# Sheet_Top_Front.net
KiCad netlist of a schematic drawn in Altium Designer
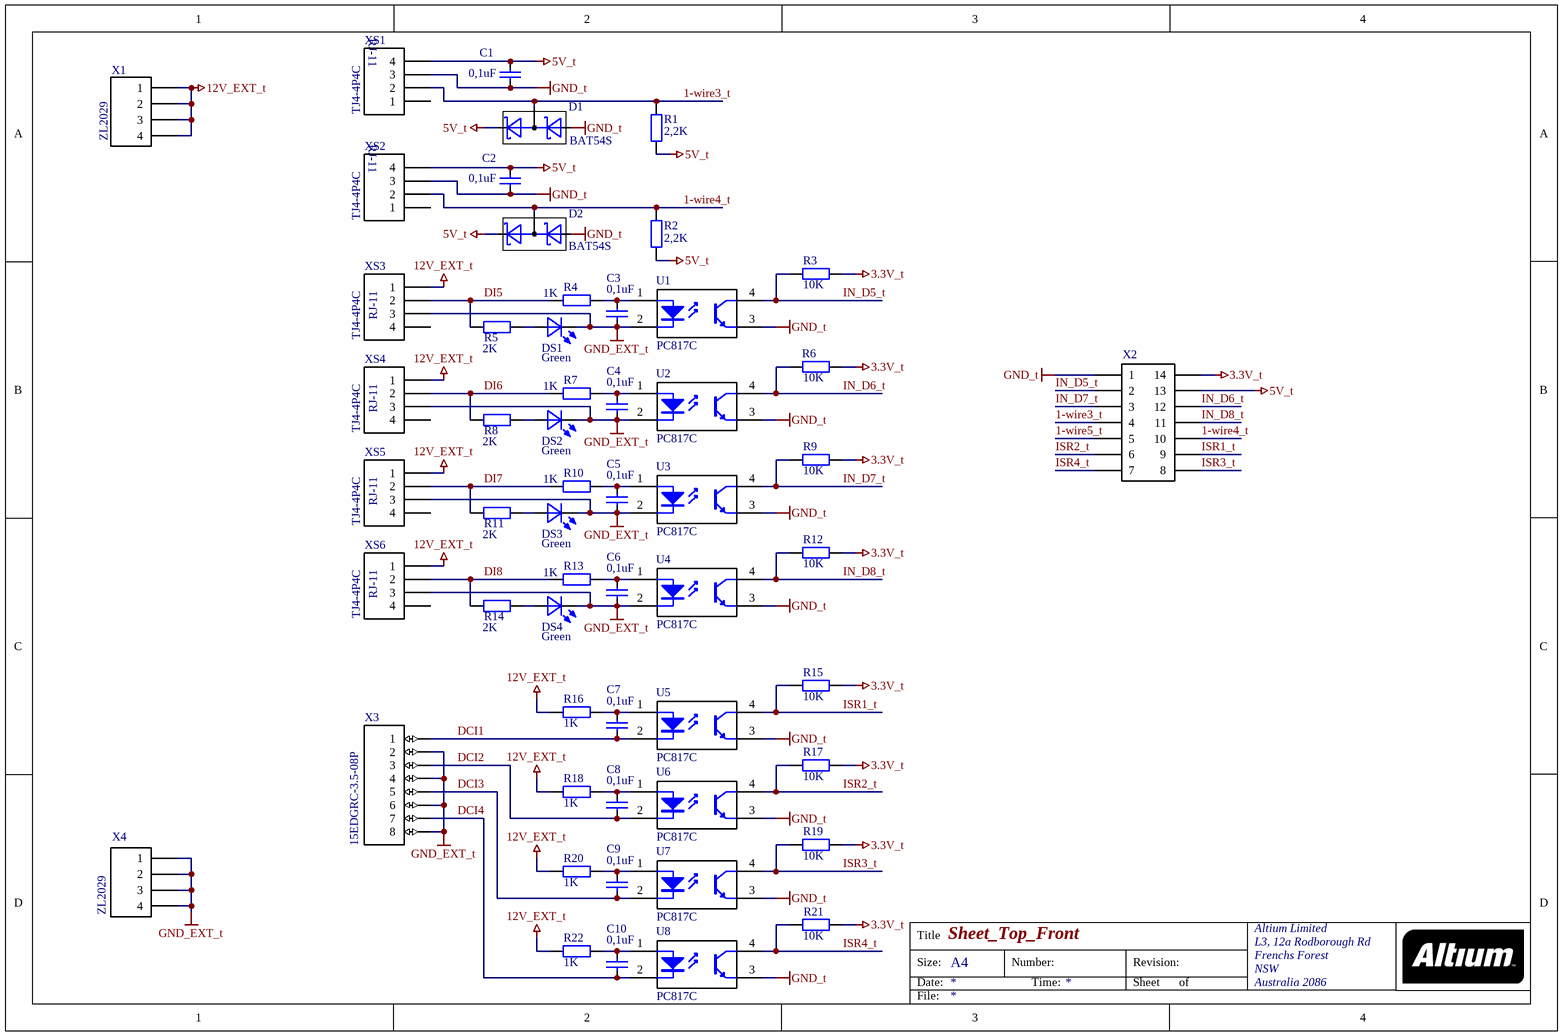
[diagram p0: Sheet_Top_Front.SchDoc]

(export (version "E")
  (design (tool "Eeschema 10.0.6"))
  (components
    (comp (ref "C1")
      (value "0,1uF")
      (footprint "C_0805")
      (description "Capacitor semi")
      (fields (field (name "Comment") "Cap_Semi"))
      (libsource (lib "Capacitor") (part "Cap_Semi"))
    )
    (comp (ref "C2")
      (value "0,1uF")
      (footprint "C_0805")
      (description "Capacitor semi")
      (fields (field (name "Comment") "Cap_Semi"))
      (libsource (lib "Capacitor") (part "Cap_Semi"))
    )
    (comp (ref "C3")
      (value "0,1uF")
      (footprint "C_0805")
      (description "Capacitor semi")
      (fields (field (name "Comment") "Cap_Semi"))
      (libsource (lib "Capacitor") (part "Cap_Semi"))
    )
    (comp (ref "C4")
      (value "0,1uF")
      (footprint "C_0805")
      (description "Capacitor semi")
      (fields (field (name "Comment") "Cap_Semi"))
      (libsource (lib "Capacitor") (part "Cap_Semi"))
    )
    (comp (ref "C5")
      (value "0,1uF")
      (footprint "C_0805")
      (description "Capacitor semi")
      (fields (field (name "Comment") "Cap_Semi"))
      (libsource (lib "Capacitor") (part "Cap_Semi"))
    )
    (comp (ref "C6")
      (value "0,1uF")
      (footprint "C_0805")
      (description "Capacitor semi")
      (fields (field (name "Comment") "Cap_Semi"))
      (libsource (lib "Capacitor") (part "Cap_Semi"))
    )
    (comp (ref "C7")
      (value "0,1uF")
      (footprint "C_0805")
      (description "Capacitor semi")
      (fields (field (name "Comment") "Cap_Semi"))
      (libsource (lib "Capacitor") (part "Cap_Semi"))
    )
    (comp (ref "C8")
      (value "0,1uF")
      (footprint "C_0805")
      (description "Capacitor semi")
      (fields (field (name "Comment") "Cap_Semi"))
      (libsource (lib "Capacitor") (part "Cap_Semi"))
    )
    (comp (ref "C9")
      (value "0,1uF")
      (footprint "C_0805")
      (description "Capacitor semi")
      (fields (field (name "Comment") "Cap_Semi"))
      (libsource (lib "Capacitor") (part "Cap_Semi"))
    )
    (comp (ref "C10")
      (value "0,1uF")
      (footprint "C_0805")
      (description "Capacitor semi")
      (fields (field (name "Comment") "Cap_Semi"))
      (libsource (lib "Capacitor") (part "Cap_Semi"))
    )
    (comp (ref "D1")
      (value "BAT54S")
      (footprint "SOT-23_d")
      (description "Diode Schottky")
      (libsource (lib "Diode") (part "BAT54S"))
    )
    (comp (ref "D2")
      (value "BAT54S")
      (footprint "SOT-23_d")
      (description "Diode Schottky")
      (libsource (lib "Diode") (part "BAT54S"))
    )
    (comp (ref "DS1")
      (value "Green")
      (footprint "LED_SMD_0805")
      (description "LED_SMD")
      (libsource (lib "LEDs") (part "LED"))
    )
    (comp (ref "DS2")
      (value "Green")
      (footprint "LED_SMD_0805")
      (description "LED_SMD")
      (libsource (lib "LEDs") (part "LED"))
    )
    (comp (ref "DS3")
      (value "Green")
      (footprint "LED_SMD_0805")
      (description "LED_SMD")
      (libsource (lib "LEDs") (part "LED"))
    )
    (comp (ref "DS4")
      (value "Green")
      (footprint "LED_SMD_0805")
      (description "LED_SMD")
      (libsource (lib "LEDs") (part "LED"))
    )
    (comp (ref "R1")
      (value "2,2K")
      (footprint "R_0805")
      (description "Resistor")
      (libsource (lib "Resistors") (part "Resistor"))
    )
    (comp (ref "R2")
      (value "2,2K")
      (footprint "R_0805")
      (description "Resistor")
      (libsource (lib "Resistors") (part "Resistor"))
    )
    (comp (ref "R3")
      (value "10K")
      (footprint "R_0805")
      (description "Resistor")
      (libsource (lib "Resistors") (part "Resistor"))
    )
    (comp (ref "R4")
      (value "1K")
      (footprint "R_0805")
      (description "Resistor")
      (libsource (lib "Resistors") (part "Resistor"))
    )
    (comp (ref "R5")
      (value "2K")
      (footprint "R_0805")
      (description "Resistor")
      (libsource (lib "Resistors") (part "Resistor"))
    )
    (comp (ref "R6")
      (value "10K")
      (footprint "R_0805")
      (description "Resistor")
      (libsource (lib "Resistors") (part "Resistor"))
    )
    (comp (ref "R7")
      (value "1K")
      (footprint "R_0805")
      (description "Resistor")
      (libsource (lib "Resistors") (part "Resistor"))
    )
    (comp (ref "R8")
      (value "2K")
      (footprint "R_0805")
      (description "Resistor")
      (libsource (lib "Resistors") (part "Resistor"))
    )
    (comp (ref "R9")
      (value "10K")
      (footprint "R_0805")
      (description "Resistor")
      (libsource (lib "Resistors") (part "Resistor"))
    )
    (comp (ref "R10")
      (value "1K")
      (footprint "R_0805")
      (description "Resistor")
      (libsource (lib "Resistors") (part "Resistor"))
    )
    (comp (ref "R11")
      (value "2K")
      (footprint "R_0805")
      (description "Resistor")
      (libsource (lib "Resistors") (part "Resistor"))
    )
    (comp (ref "R12")
      (value "10K")
      (footprint "R_0805")
      (description "Resistor")
      (libsource (lib "Resistors") (part "Resistor"))
    )
    (comp (ref "R13")
      (value "1K")
      (footprint "R_0805")
      (description "Resistor")
      (libsource (lib "Resistors") (part "Resistor"))
    )
    (comp (ref "R14")
      (value "2K")
      (footprint "R_0805")
      (description "Resistor")
      (libsource (lib "Resistors") (part "Resistor"))
    )
    (comp (ref "R15")
      (value "10K")
      (footprint "R_0805")
      (description "Resistor")
      (libsource (lib "Resistors") (part "Resistor"))
    )
    (comp (ref "R16")
      (value "1K")
      (footprint "R_0805")
      (description "Resistor")
      (libsource (lib "Resistors") (part "Resistor"))
    )
    (comp (ref "R17")
      (value "10K")
      (footprint "R_0805")
      (description "Resistor")
      (libsource (lib "Resistors") (part "Resistor"))
    )
    (comp (ref "R18")
      (value "1K")
      (footprint "R_0805")
      (description "Resistor")
      (libsource (lib "Resistors") (part "Resistor"))
    )
    (comp (ref "R19")
      (value "10K")
      (footprint "R_0805")
      (description "Resistor")
      (libsource (lib "Resistors") (part "Resistor"))
    )
    (comp (ref "R20")
      (value "1K")
      (footprint "R_0805")
      (description "Resistor")
      (libsource (lib "Resistors") (part "Resistor"))
    )
    (comp (ref "R21")
      (value "10K")
      (footprint "R_0805")
      (description "Resistor")
      (libsource (lib "Resistors") (part "Resistor"))
    )
    (comp (ref "R22")
      (value "1K")
      (footprint "R_0805")
      (description "Resistor")
      (libsource (lib "Resistors") (part "Resistor"))
    )
    (comp (ref "U1")
      (value "PC817C")
      (footprint "DIP-4")
      (description "Optocoupler")
      (libsource (lib "Chip_Packaging") (part "PC817"))
    )
    (comp (ref "U2")
      (value "PC817C")
      (footprint "DIP-4")
      (description "Optocoupler")
      (libsource (lib "Chip_Packaging") (part "PC817"))
    )
    (comp (ref "U3")
      (value "PC817C")
      (footprint "DIP-4")
      (description "Optocoupler")
      (libsource (lib "Chip_Packaging") (part "PC817"))
    )
    (comp (ref "U4")
      (value "PC817C")
      (footprint "DIP-4")
      (description "Optocoupler")
      (libsource (lib "Chip_Packaging") (part "PC817"))
    )
    (comp (ref "U5")
      (value "PC817C")
      (footprint "DIP-4")
      (description "Optocoupler")
      (libsource (lib "Chip_Packaging") (part "PC817"))
    )
    (comp (ref "U6")
      (value "PC817C")
      (footprint "DIP-4")
      (description "Optocoupler")
      (libsource (lib "Chip_Packaging") (part "PC817"))
    )
    (comp (ref "U7")
      (value "PC817C")
      (footprint "DIP-4")
      (description "Optocoupler")
      (libsource (lib "Chip_Packaging") (part "PC817"))
    )
    (comp (ref "U8")
      (value "PC817C")
      (footprint "DIP-4")
      (description "Optocoupler")
      (libsource (lib "Chip_Packaging") (part "PC817"))
    )
    (comp (ref "X1")
      (value "ZL2029")
      (footprint "PLS-4-3D")
      (description "Header, 4-Pin")
      (fields (field (name "ALTIUM_UNNAMED_1") "ZL2029") (field (name "PUBLISHER") "Altium Limited"))
      (libsource (lib "Connect") (part "PLS-4"))
    )
    (comp (ref "X2")
      (value "PLS2-14")
      (footprint "PLS2-14")
      (description "Header, 14-Pin")
      (libsource (lib "Connect") (part "PLS2-14"))
    )
    (comp (ref "X3")
      (value "15EDGRC-3.5-08P")
      (footprint "MC_3.5_8")
      (description "Connector 3.5mm")
      (libsource (lib "Connect") (part "MC_3.5_8"))
    )
    (comp (ref "X4")
      (value "PLS-4")
      (footprint "PLS-4-3D")
      (description "ZL2029")
      (fields (field (name "ALTIUM_UNNAMED_1") "ZL2029") (field (name "PUBLISHER") "Altium Limited"))
      (libsource (lib "Connect") (part "PLS-4"))
    )
    (comp (ref "XS1")
      (value "RJ-11")
      (footprint "RJ-11 - TJ4-4P4C")
      (description "TJ4-4P4C")
      (fields (field (name "ALTIUM_UNNAMED_1") "TJ4-4P4C"))
      (libsource (lib "") (part "RJ-11_1"))
    )
    (comp (ref "XS2")
      (value "RJ-11")
      (footprint "RJ-11 - TJ4-4P4C")
      (description "TJ4-4P4C")
      (fields (field (name "ALTIUM_UNNAMED_1") "TJ4-4P4C"))
      (libsource (lib "") (part "RJ-11_1"))
    )
    (comp (ref "XS3")
      (value "RJ-11")
      (footprint "RJ-11 - TJ4-4P4C")
      (description "TJ4-4P4C")
      (fields (field (name "ALTIUM_UNNAMED_1") "TJ4-4P4C"))
      (libsource (lib "Connect") (part "RJ-11"))
    )
    (comp (ref "XS4")
      (value "RJ-11")
      (footprint "RJ-11 - TJ4-4P4C")
      (description "TJ4-4P4C")
      (fields (field (name "ALTIUM_UNNAMED_1") "TJ4-4P4C"))
      (libsource (lib "Connect") (part "RJ-11"))
    )
    (comp (ref "XS5")
      (value "RJ-11")
      (footprint "RJ-11 - TJ4-4P4C")
      (description "TJ4-4P4C")
      (fields (field (name "ALTIUM_UNNAMED_1") "TJ4-4P4C"))
      (libsource (lib "Connect") (part "RJ-11"))
    )
    (comp (ref "XS6")
      (value "RJ-11")
      (footprint "RJ-11 - TJ4-4P4C")
      (description "TJ4-4P4C")
      (fields (field (name "ALTIUM_UNNAMED_1") "TJ4-4P4C"))
      (libsource (lib "Connect") (part "RJ-11"))
    )
  )
  (nets
    (net (code "1") (name "/1-wire3_t") (class "Default")
      (node (ref "D1") (pin "3") (pinfunction "CA_3") (pintype "passive"))
      (node (ref "R1") (pin "1") (pinfunction "1_1") (pintype "passive"))
      (node (ref "X2") (pin "4") (pinfunction "4_4") (pintype "passive"))
      (node (ref "XS1") (pin "2") (pinfunction "2_2") (pintype "passive"))
    )
    (net (code "2") (name "/1-wire4_t") (class "Default")
      (node (ref "D2") (pin "3") (pinfunction "CA_3") (pintype "passive"))
      (node (ref "R2") (pin "1") (pinfunction "1_1") (pintype "passive"))
      (node (ref "X2") (pin "10") (pinfunction "10_10") (pintype "passive"))
      (node (ref "XS2") (pin "2") (pinfunction "2_2") (pintype "passive"))
    )
    (net (code "3") (name "/1-wire5_t") (class "Default")
      (node (ref "X2") (pin "5") (pinfunction "5_5") (pintype "passive"))
    )
    (net (code "4") (name "/DCI1") (class "Default")
      (node (ref "C7") (pin "2") (pinfunction "2_2") (pintype "passive"))
      (node (ref "U5") (pin "2") (pinfunction "K_2") (pintype "passive"))
      (node (ref "X3") (pin "1") (pinfunction "1_1") (pintype "bidirectional"))
    )
    (net (code "5") (name "/DCI2") (class "Default")
      (node (ref "C8") (pin "2") (pinfunction "2_2") (pintype "passive"))
      (node (ref "U6") (pin "2") (pinfunction "K_2") (pintype "passive"))
      (node (ref "X3") (pin "3") (pinfunction "3_3") (pintype "bidirectional"))
    )
    (net (code "6") (name "/DCI3") (class "Default")
      (node (ref "C9") (pin "2") (pinfunction "2_2") (pintype "passive"))
      (node (ref "U7") (pin "2") (pinfunction "K_2") (pintype "passive"))
      (node (ref "X3") (pin "5") (pinfunction "5_5") (pintype "bidirectional"))
    )
    (net (code "7") (name "/DCI4") (class "Default")
      (node (ref "C10") (pin "2") (pinfunction "2_2") (pintype "passive"))
      (node (ref "U8") (pin "2") (pinfunction "K_2") (pintype "passive"))
      (node (ref "X3") (pin "7") (pinfunction "7_7") (pintype "bidirectional"))
    )
    (net (code "8") (name "/DI5") (class "Default")
      (node (ref "R4") (pin "2") (pinfunction "2_2") (pintype "passive"))
      (node (ref "R5") (pin "2") (pinfunction "2_2") (pintype "passive"))
      (node (ref "XS3") (pin "2") (pinfunction "2_2") (pintype "passive"))
    )
    (net (code "9") (name "/DI6") (class "Default")
      (node (ref "R7") (pin "2") (pinfunction "2_2") (pintype "passive"))
      (node (ref "R8") (pin "2") (pinfunction "2_2") (pintype "passive"))
      (node (ref "XS4") (pin "2") (pinfunction "2_2") (pintype "passive"))
    )
    (net (code "10") (name "/DI7") (class "Default")
      (node (ref "R10") (pin "2") (pinfunction "2_2") (pintype "passive"))
      (node (ref "R11") (pin "2") (pinfunction "2_2") (pintype "passive"))
      (node (ref "XS5") (pin "2") (pinfunction "2_2") (pintype "passive"))
    )
    (net (code "11") (name "/DI8") (class "Default")
      (node (ref "R13") (pin "2") (pinfunction "2_2") (pintype "passive"))
      (node (ref "R14") (pin "2") (pinfunction "2_2") (pintype "passive"))
      (node (ref "XS6") (pin "2") (pinfunction "2_2") (pintype "passive"))
    )
    (net (code "12") (name "/IN_D5_t") (class "Default")
      (node (ref "R3") (pin "2") (pinfunction "2_2") (pintype "passive"))
      (node (ref "U1") (pin "4") (pinfunction "C_4") (pintype "passive"))
      (node (ref "X2") (pin "2") (pinfunction "2_2") (pintype "passive"))
    )
    (net (code "13") (name "/IN_D6_t") (class "Default")
      (node (ref "R6") (pin "2") (pinfunction "2_2") (pintype "passive"))
      (node (ref "U2") (pin "4") (pinfunction "C_4") (pintype "passive"))
      (node (ref "X2") (pin "12") (pinfunction "12_12") (pintype "passive"))
    )
    (net (code "14") (name "/IN_D7_t") (class "Default")
      (node (ref "R9") (pin "2") (pinfunction "2_2") (pintype "passive"))
      (node (ref "U3") (pin "4") (pinfunction "C_4") (pintype "passive"))
      (node (ref "X2") (pin "3") (pinfunction "3_3") (pintype "passive"))
    )
    (net (code "15") (name "/IN_D8_t") (class "Default")
      (node (ref "R12") (pin "2") (pinfunction "2_2") (pintype "passive"))
      (node (ref "U4") (pin "4") (pinfunction "C_4") (pintype "passive"))
      (node (ref "X2") (pin "11") (pinfunction "11_11") (pintype "passive"))
    )
    (net (code "16") (name "/ISR1_t") (class "Default")
      (node (ref "R15") (pin "2") (pinfunction "2_2") (pintype "passive"))
      (node (ref "U5") (pin "4") (pinfunction "C_4") (pintype "passive"))
      (node (ref "X2") (pin "9") (pinfunction "9_9") (pintype "passive"))
    )
    (net (code "17") (name "/ISR2_t") (class "Default")
      (node (ref "R17") (pin "2") (pinfunction "2_2") (pintype "passive"))
      (node (ref "U6") (pin "4") (pinfunction "C_4") (pintype "passive"))
      (node (ref "X2") (pin "6") (pinfunction "6_6") (pintype "passive"))
    )
    (net (code "18") (name "/ISR3_t") (class "Default")
      (node (ref "R19") (pin "2") (pinfunction "2_2") (pintype "passive"))
      (node (ref "U7") (pin "4") (pinfunction "C_4") (pintype "passive"))
      (node (ref "X2") (pin "8") (pinfunction "8_8") (pintype "passive"))
    )
    (net (code "19") (name "/ISR4_t") (class "Default")
      (node (ref "R21") (pin "2") (pinfunction "2_2") (pintype "passive"))
      (node (ref "U8") (pin "4") (pinfunction "C_4") (pintype "passive"))
      (node (ref "X2") (pin "7") (pinfunction "7_7") (pintype "passive"))
    )
    (net (code "20") (name "3.3V_t") (class "Default")
      (node (ref "R12") (pin "1") (pinfunction "1_1") (pintype "passive"))
      (node (ref "R15") (pin "1") (pinfunction "1_1") (pintype "passive"))
      (node (ref "R17") (pin "1") (pinfunction "1_1") (pintype "passive"))
      (node (ref "R19") (pin "1") (pinfunction "1_1") (pintype "passive"))
      (node (ref "R21") (pin "1") (pinfunction "1_1") (pintype "passive"))
      (node (ref "R3") (pin "1") (pinfunction "1_1") (pintype "passive"))
      (node (ref "R6") (pin "1") (pinfunction "1_1") (pintype "passive"))
      (node (ref "R9") (pin "1") (pinfunction "1_1") (pintype "passive"))
      (node (ref "X2") (pin "14") (pinfunction "14_14") (pintype "passive"))
    )
    (net (code "21") (name "5V_t") (class "Default")
      (node (ref "C1") (pin "1") (pinfunction "1_1") (pintype "passive"))
      (node (ref "C2") (pin "1") (pinfunction "1_1") (pintype "passive"))
      (node (ref "D1") (pin "2") (pinfunction "C_2") (pintype "passive"))
      (node (ref "D2") (pin "2") (pinfunction "C_2") (pintype "passive"))
      (node (ref "R1") (pin "2") (pinfunction "2_2") (pintype "passive"))
      (node (ref "R2") (pin "2") (pinfunction "2_2") (pintype "passive"))
      (node (ref "X2") (pin "13") (pinfunction "13_13") (pintype "passive"))
      (node (ref "XS1") (pin "4") (pinfunction "4_4") (pintype "passive"))
      (node (ref "XS2") (pin "4") (pinfunction "4_4") (pintype "passive"))
    )
    (net (code "22") (name "12V_EXT_t") (class "Default")
      (node (ref "R16") (pin "2") (pinfunction "2_2") (pintype "passive"))
      (node (ref "R18") (pin "2") (pinfunction "2_2") (pintype "passive"))
      (node (ref "R20") (pin "2") (pinfunction "2_2") (pintype "passive"))
      (node (ref "R22") (pin "2") (pinfunction "2_2") (pintype "passive"))
      (node (ref "X1") (pin "1") (pinfunction "1_1") (pintype "passive"))
      (node (ref "X1") (pin "2") (pinfunction "2_2") (pintype "passive"))
      (node (ref "X1") (pin "3") (pinfunction "3_3") (pintype "passive"))
      (node (ref "X1") (pin "4") (pinfunction "4_4") (pintype "passive"))
      (node (ref "XS3") (pin "1") (pinfunction "1_1") (pintype "passive"))
      (node (ref "XS4") (pin "1") (pinfunction "1_1") (pintype "passive"))
      (node (ref "XS5") (pin "1") (pinfunction "1_1") (pintype "passive"))
      (node (ref "XS6") (pin "1") (pinfunction "1_1") (pintype "passive"))
    )
    (net (code "23") (name "GND_EXT_t") (class "Default")
      (node (ref "C3") (pin "2") (pinfunction "2_2") (pintype "passive"))
      (node (ref "C4") (pin "2") (pinfunction "2_2") (pintype "passive"))
      (node (ref "C5") (pin "2") (pinfunction "2_2") (pintype "passive"))
      (node (ref "C6") (pin "2") (pinfunction "2_2") (pintype "passive"))
      (node (ref "DS1") (pin "2") (pinfunction "C_2") (pintype "passive"))
      (node (ref "DS2") (pin "2") (pinfunction "C_2") (pintype "passive"))
      (node (ref "DS3") (pin "2") (pinfunction "C_2") (pintype "passive"))
      (node (ref "DS4") (pin "2") (pinfunction "C_2") (pintype "passive"))
      (node (ref "U1") (pin "2") (pinfunction "K_2") (pintype "passive"))
      (node (ref "U2") (pin "2") (pinfunction "K_2") (pintype "passive"))
      (node (ref "U3") (pin "2") (pinfunction "K_2") (pintype "passive"))
      (node (ref "U4") (pin "2") (pinfunction "K_2") (pintype "passive"))
      (node (ref "X3") (pin "2") (pinfunction "2_2") (pintype "bidirectional"))
      (node (ref "X3") (pin "4") (pinfunction "4_4") (pintype "bidirectional"))
      (node (ref "X3") (pin "6") (pinfunction "6_6") (pintype "bidirectional"))
      (node (ref "X3") (pin "8") (pinfunction "8_8") (pintype "bidirectional"))
      (node (ref "X4") (pin "1") (pinfunction "1_1") (pintype "passive"))
      (node (ref "X4") (pin "2") (pinfunction "2_2") (pintype "passive"))
      (node (ref "X4") (pin "3") (pinfunction "3_3") (pintype "passive"))
      (node (ref "X4") (pin "4") (pinfunction "4_4") (pintype "passive"))
      (node (ref "XS3") (pin "3") (pinfunction "3_3") (pintype "passive"))
      (node (ref "XS4") (pin "3") (pinfunction "3_3") (pintype "passive"))
      (node (ref "XS5") (pin "3") (pinfunction "3_3") (pintype "passive"))
      (node (ref "XS6") (pin "3") (pinfunction "3_3") (pintype "passive"))
    )
    (net (code "24") (name "GND_t") (class "Default")
      (node (ref "C1") (pin "2") (pinfunction "2_2") (pintype "passive"))
      (node (ref "C2") (pin "2") (pinfunction "2_2") (pintype "passive"))
      (node (ref "D1") (pin "1") (pinfunction "A_1") (pintype "passive"))
      (node (ref "D2") (pin "1") (pinfunction "A_1") (pintype "passive"))
      (node (ref "U1") (pin "3") (pinfunction "E_3") (pintype "passive"))
      (node (ref "U2") (pin "3") (pinfunction "E_3") (pintype "passive"))
      (node (ref "U3") (pin "3") (pinfunction "E_3") (pintype "passive"))
      (node (ref "U4") (pin "3") (pinfunction "E_3") (pintype "passive"))
      (node (ref "U5") (pin "3") (pinfunction "E_3") (pintype "passive"))
      (node (ref "U6") (pin "3") (pinfunction "E_3") (pintype "passive"))
      (node (ref "U7") (pin "3") (pinfunction "E_3") (pintype "passive"))
      (node (ref "U8") (pin "3") (pinfunction "E_3") (pintype "passive"))
      (node (ref "X2") (pin "1") (pinfunction "1_1") (pintype "passive"))
      (node (ref "XS1") (pin "3") (pinfunction "3_3") (pintype "passive"))
      (node (ref "XS2") (pin "3") (pinfunction "3_3") (pintype "passive"))
    )
    (net (code "25") (name "Net-(DS1-A)") (class "Default")
      (node (ref "DS1") (pin "1") (pinfunction "A_1") (pintype "passive"))
      (node (ref "R5") (pin "1") (pinfunction "1_1") (pintype "passive"))
    )
    (net (code "26") (name "Net-(DS2-A)") (class "Default")
      (node (ref "DS2") (pin "1") (pinfunction "A_1") (pintype "passive"))
      (node (ref "R8") (pin "1") (pinfunction "1_1") (pintype "passive"))
    )
    (net (code "27") (name "Net-(DS3-A)") (class "Default")
      (node (ref "DS3") (pin "1") (pinfunction "A_1") (pintype "passive"))
      (node (ref "R11") (pin "1") (pinfunction "1_1") (pintype "passive"))
    )
    (net (code "28") (name "Net-(DS4-A)") (class "Default")
      (node (ref "DS4") (pin "1") (pinfunction "A_1") (pintype "passive"))
      (node (ref "R14") (pin "1") (pinfunction "1_1") (pintype "passive"))
    )
    (net (code "29") (name "Net-(U1-A)") (class "Default")
      (node (ref "C3") (pin "1") (pinfunction "1_1") (pintype "passive"))
      (node (ref "R4") (pin "1") (pinfunction "1_1") (pintype "passive"))
      (node (ref "U1") (pin "1") (pinfunction "A_1") (pintype "passive"))
    )
    (net (code "30") (name "Net-(U2-A)") (class "Default")
      (node (ref "C4") (pin "1") (pinfunction "1_1") (pintype "passive"))
      (node (ref "R7") (pin "1") (pinfunction "1_1") (pintype "passive"))
      (node (ref "U2") (pin "1") (pinfunction "A_1") (pintype "passive"))
    )
    (net (code "31") (name "Net-(U3-A)") (class "Default")
      (node (ref "C5") (pin "1") (pinfunction "1_1") (pintype "passive"))
      (node (ref "R10") (pin "1") (pinfunction "1_1") (pintype "passive"))
      (node (ref "U3") (pin "1") (pinfunction "A_1") (pintype "passive"))
    )
    (net (code "32") (name "Net-(U4-A)") (class "Default")
      (node (ref "C6") (pin "1") (pinfunction "1_1") (pintype "passive"))
      (node (ref "R13") (pin "1") (pinfunction "1_1") (pintype "passive"))
      (node (ref "U4") (pin "1") (pinfunction "A_1") (pintype "passive"))
    )
    (net (code "33") (name "Net-(U5-A)") (class "Default")
      (node (ref "C7") (pin "1") (pinfunction "1_1") (pintype "passive"))
      (node (ref "R16") (pin "1") (pinfunction "1_1") (pintype "passive"))
      (node (ref "U5") (pin "1") (pinfunction "A_1") (pintype "passive"))
    )
    (net (code "34") (name "Net-(U6-A)") (class "Default")
      (node (ref "C8") (pin "1") (pinfunction "1_1") (pintype "passive"))
      (node (ref "R18") (pin "1") (pinfunction "1_1") (pintype "passive"))
      (node (ref "U6") (pin "1") (pinfunction "A_1") (pintype "passive"))
    )
    (net (code "35") (name "Net-(U7-A)") (class "Default")
      (node (ref "C9") (pin "1") (pinfunction "1_1") (pintype "passive"))
      (node (ref "R20") (pin "1") (pinfunction "1_1") (pintype "passive"))
      (node (ref "U7") (pin "1") (pinfunction "A_1") (pintype "passive"))
    )
    (net (code "36") (name "Net-(U8-A)") (class "Default")
      (node (ref "C10") (pin "1") (pinfunction "1_1") (pintype "passive"))
      (node (ref "R22") (pin "1") (pinfunction "1_1") (pintype "passive"))
      (node (ref "U8") (pin "1") (pinfunction "A_1") (pintype "passive"))
    )
    (net (code "37") (name "unconnected-(XS1-Pad1)") (class "Default")
      (node (ref "XS1") (pin "1") (pinfunction "1_1") (pintype "passive"))
    )
    (net (code "38") (name "unconnected-(XS2-Pad1)") (class "Default")
      (node (ref "XS2") (pin "1") (pinfunction "1_1") (pintype "passive"))
    )
    (net (code "39") (name "unconnected-(XS3-Pad4)") (class "Default")
      (node (ref "XS3") (pin "4") (pinfunction "4_4") (pintype "passive"))
    )
    (net (code "40") (name "unconnected-(XS4-Pad4)") (class "Default")
      (node (ref "XS4") (pin "4") (pinfunction "4_4") (pintype "passive"))
    )
    (net (code "41") (name "unconnected-(XS5-Pad4)") (class "Default")
      (node (ref "XS5") (pin "4") (pinfunction "4_4") (pintype "passive"))
    )
    (net (code "42") (name "unconnected-(XS6-Pad4)") (class "Default")
      (node (ref "XS6") (pin "4") (pinfunction "4_4") (pintype "passive"))
    )
  )
)
